# Esquematico_microcotrolador_actuador1.net
KiCad netlist of a schematic drawn in Altium Designer
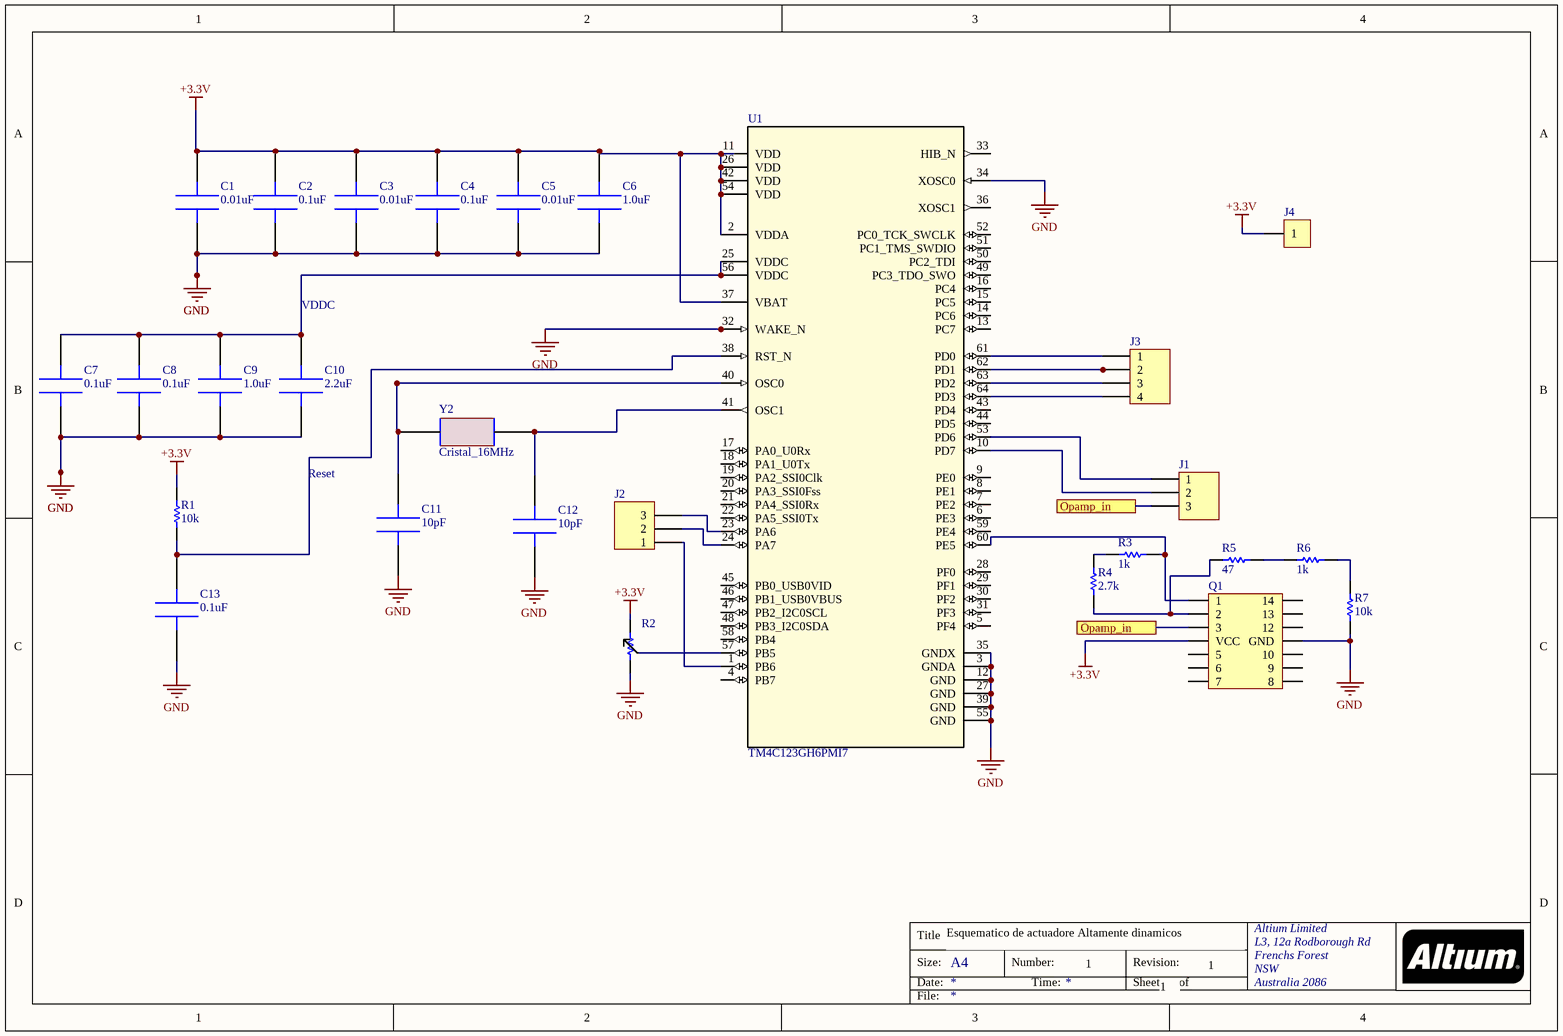
[diagram p0: Esquematico_microcotrolador_actuador1.SchDoc]

(export (version "E")
  (design (tool "Eeschema 10.0.6"))
  (components
    (comp (ref "C1")
      (value "0.01uF")
      (footprint "Capacitor")
      (libsource (lib "esquematicos_librerias") (part "CAP_0.01uF"))
    )
    (comp (ref "C2")
      (value "0.1uF")
      (footprint "Capacitor")
      (libsource (lib "esquematicos_librerias") (part "CAP_0.01uF"))
    )
    (comp (ref "C3")
      (value "0.01uF")
      (footprint "Capacitor")
      (libsource (lib "esquematicos_librerias") (part "CAP_0.01uF"))
    )
    (comp (ref "C4")
      (value "0.1uF")
      (footprint "Capacitor")
      (libsource (lib "esquematicos_librerias") (part "CAP_0.01uF"))
    )
    (comp (ref "C5")
      (value "0.01uF")
      (footprint "Capacitor")
      (libsource (lib "esquematicos_librerias") (part "CAP_0.01uF"))
    )
    (comp (ref "C6")
      (value "1.0uF")
      (footprint "Capacitor")
      (libsource (lib "esquematicos_librerias") (part "CAP_0.01uF"))
    )
    (comp (ref "C7")
      (value "0.1uF")
      (footprint "Capacitor")
      (libsource (lib "esquematicos_librerias") (part "CAP_0.01uF"))
    )
    (comp (ref "C8")
      (value "0.1uF")
      (footprint "Capacitor")
      (libsource (lib "esquematicos_librerias") (part "CAP_0.01uF"))
    )
    (comp (ref "C9")
      (value "1.0uF")
      (footprint "Capacitor")
      (libsource (lib "esquematicos_librerias") (part "CAP_0.01uF"))
    )
    (comp (ref "C10")
      (value "2.2uF")
      (footprint "Capacitor")
      (libsource (lib "esquematicos_librerias") (part "CAP_0.01uF"))
    )
    (comp (ref "C11")
      (value "10pF")
      (footprint "Capacitor")
      (libsource (lib "esquematicos_librerias") (part "CAP_0.01uF"))
    )
    (comp (ref "C12")
      (value "10pF")
      (footprint "Capacitor")
      (libsource (lib "esquematicos_librerias") (part "CAP_0.01uF"))
    )
    (comp (ref "C13")
      (value "0.1uF")
      (footprint "Capacitor")
      (libsource (lib "esquematicos_librerias") (part "CAP_0.01uF"))
    )
    (comp (ref "J1") (value "HEADERS") (footprint "2_PIN_HEADER") (libsource (lib "") (part "HEADERS_1")))
    (comp (ref "J2")
      (value "HEADERS")
      (footprint "2_PIN_HEADER")
      (libsource (lib "esquematicos_librerias") (part "HEADERS"))
    )
    (comp (ref "J3")
      (value "4_HEADERS")
      (footprint "4_HEADERS")
      (libsource (lib "esquematicos_librerias") (part "4_HEADERS"))
    )
    (comp (ref "J4")
      (value "1_HEADER")
      (footprint "1_HEADER")
      (libsource (lib "esquematicos_librerias") (part "1_HEADER"))
    )
    (comp (ref "Q1")
      (value "Op-amp")
      (footprint "Op-amp")
      (libsource (lib "esquematicos_librerias") (part "Op-amp"))
    )
    (comp (ref "R1")
      (value "10k")
      (footprint "resistencia")
      (libsource (lib "esquematicos_librerias") (part "Resisistencia"))
    )
    (comp (ref "R2")
      (value "potenciometro")
      (footprint "Potenciometro")
      (libsource (lib "esquematicos_librerias") (part "potenciometro"))
    )
    (comp (ref "R3")
      (value "1k")
      (footprint "resistencia")
      (libsource (lib "esquematicos_librerias") (part "Resisistencia"))
    )
    (comp (ref "R4")
      (value "2.7k")
      (footprint "resistencia")
      (libsource (lib "esquematicos_librerias") (part "Resisistencia"))
    )
    (comp (ref "R5")
      (value "47")
      (footprint "resistencia")
      (libsource (lib "esquematicos_librerias") (part "Resisistencia"))
    )
    (comp (ref "R6")
      (value "1k")
      (footprint "resistencia")
      (libsource (lib "esquematicos_librerias") (part "Resisistencia"))
    )
    (comp (ref "R7")
      (value "10k")
      (footprint "resistencia")
      (libsource (lib "esquematicos_librerias") (part "Resisistencia"))
    )
    (comp (ref "U1")
      (value "TM4C123GH6PMI7")
      (footprint "PM0064A_N")
      (description "No Description Available")
      (fields
        (field (name "PARTNUMBER") "TM4C123GH6PMTR")
        (field (name "ALTERNATE_PARTNUMBER") "TM4C123GH6PMT")
        (field (name "COPYRIGHT") "Copyright (C) 2021 Ultra Librarian. All rights reserved.")
      )
      (libsource (lib "esquematicos_librerias") (part "TM4C123GH6PMI7"))
    )
    (comp (ref "Y2")
      (value "Cristal_16MHz")
      (footprint "cristal_16MHz")
      (libsource (lib "esquematicos_librerias") (part "Cristal_16MHz"))
    )
  )
  (nets
    (net (code "1") (name "+3.3V") (class "Default")
      (node (ref "C1") (pin "2") (pinfunction "10_2") (pintype "passive"))
      (node (ref "C2") (pin "2") (pinfunction "10_2") (pintype "passive"))
      (node (ref "C3") (pin "2") (pinfunction "10_2") (pintype "passive"))
      (node (ref "C4") (pin "2") (pinfunction "10_2") (pintype "passive"))
      (node (ref "C5") (pin "2") (pinfunction "10_2") (pintype "passive"))
      (node (ref "C6") (pin "2") (pinfunction "10_2") (pintype "passive"))
      (node (ref "J4") (pin "1") (pinfunction "1_1") (pintype "passive"))
      (node (ref "Q1") (pin "4") (pinfunction "VCC_4") (pintype "passive"))
      (node (ref "R1") (pin "2") (pinfunction "2_2") (pintype "passive"))
      (node (ref "R2") (pin "2") (pinfunction "2_2") (pintype "passive"))
      (node (ref "U1") (pin "11") (pinfunction "VDD_11") (pintype "power_in"))
      (node (ref "U1") (pin "2") (pinfunction "VDDA_2") (pintype "power_in"))
      (node (ref "U1") (pin "26") (pinfunction "VDD_26") (pintype "power_in"))
      (node (ref "U1") (pin "37") (pinfunction "VBAT_37") (pintype "power_in"))
      (node (ref "U1") (pin "42") (pinfunction "VDD_42") (pintype "power_in"))
      (node (ref "U1") (pin "54") (pinfunction "VDD_54") (pintype "power_in"))
    )
    (net (code "2") (name "/Opamp_in") (class "Default")
      (node (ref "J1") (pin "3") (pinfunction "3_3") (pintype "passive"))
      (node (ref "Q1") (pin "3") (pinfunction "3_3") (pintype "passive"))
    )
    (net (code "3") (name "GND") (class "Default")
      (node (ref "C1") (pin "1") (pinfunction "9_1") (pintype "passive"))
      (node (ref "C10") (pin "1") (pinfunction "9_1") (pintype "passive"))
      (node (ref "C11") (pin "2") (pinfunction "10_2") (pintype "passive"))
      (node (ref "C12") (pin "2") (pinfunction "10_2") (pintype "passive"))
      (node (ref "C13") (pin "1") (pinfunction "9_1") (pintype "passive"))
      (node (ref "C2") (pin "1") (pinfunction "9_1") (pintype "passive"))
      (node (ref "C3") (pin "1") (pinfunction "9_1") (pintype "passive"))
      (node (ref "C4") (pin "1") (pinfunction "9_1") (pintype "passive"))
      (node (ref "C5") (pin "1") (pinfunction "9_1") (pintype "passive"))
      (node (ref "C6") (pin "1") (pinfunction "9_1") (pintype "passive"))
      (node (ref "C7") (pin "1") (pinfunction "9_1") (pintype "passive"))
      (node (ref "C8") (pin "1") (pinfunction "9_1") (pintype "passive"))
      (node (ref "C9") (pin "1") (pinfunction "9_1") (pintype "passive"))
      (node (ref "Q1") (pin "11") (pinfunction "GND_11") (pintype "passive"))
      (node (ref "R2") (pin "1") (pinfunction "1_1") (pintype "passive"))
      (node (ref "R7") (pin "2") (pinfunction "2_2") (pintype "passive"))
      (node (ref "U1") (pin "12") (pinfunction "GND_12") (pintype "power_in"))
      (node (ref "U1") (pin "27") (pinfunction "GND_27") (pintype "power_in"))
      (node (ref "U1") (pin "3") (pinfunction "GNDA_3") (pintype "power_in"))
      (node (ref "U1") (pin "32") (pinfunction "WAKE_N_32") (pintype "input"))
      (node (ref "U1") (pin "34") (pinfunction "XOSC0_34") (pintype "input"))
      (node (ref "U1") (pin "35") (pinfunction "GNDX_35") (pintype "power_in"))
      (node (ref "U1") (pin "39") (pinfunction "GND_39") (pintype "power_in"))
      (node (ref "U1") (pin "55") (pinfunction "GND_55") (pintype "power_in"))
    )
    (net (code "4") (name "Net-(C10-10)") (class "Default")
      (node (ref "C10") (pin "2") (pinfunction "10_2") (pintype "passive"))
      (node (ref "C7") (pin "2") (pinfunction "10_2") (pintype "passive"))
      (node (ref "C8") (pin "2") (pinfunction "10_2") (pintype "passive"))
      (node (ref "C9") (pin "2") (pinfunction "10_2") (pintype "passive"))
      (node (ref "U1") (pin "25") (pinfunction "VDDC_25") (pintype "power_in"))
      (node (ref "U1") (pin "56") (pinfunction "VDDC_56") (pintype "power_in"))
    )
    (net (code "5") (name "Net-(C11-9)") (class "Default")
      (node (ref "C11") (pin "1") (pinfunction "9_1") (pintype "passive"))
      (node (ref "U1") (pin "40") (pinfunction "OSC0_40") (pintype "input"))
      (node (ref "Y2") (pin "1") (pinfunction "73_1") (pintype "passive"))
    )
    (net (code "6") (name "Net-(C12-9)") (class "Default")
      (node (ref "C12") (pin "1") (pinfunction "9_1") (pintype "passive"))
      (node (ref "U1") (pin "41") (pinfunction "OSC1_41") (pintype "output"))
      (node (ref "Y2") (pin "2") (pinfunction "74_2") (pintype "passive"))
    )
    (net (code "7") (name "Net-(C13-10)") (class "Default")
      (node (ref "C13") (pin "2") (pinfunction "10_2") (pintype "passive"))
      (node (ref "R1") (pin "1") (pinfunction "1_1") (pintype "passive"))
      (node (ref "U1") (pin "38") (pinfunction "RST_N_38") (pintype "input"))
    )
    (net (code "8") (name "Net-(Q1-Pad2)") (class "Default")
      (node (ref "Q1") (pin "2") (pinfunction "2_2") (pintype "passive"))
      (node (ref "R4") (pin "1") (pinfunction "1_1") (pintype "passive"))
      (node (ref "R5") (pin "2") (pinfunction "2_2") (pintype "passive"))
    )
    (net (code "9") (name "Net-(R3-Pad2)") (class "Default")
      (node (ref "R3") (pin "2") (pinfunction "2_2") (pintype "passive"))
      (node (ref "R4") (pin "2") (pinfunction "2_2") (pintype "passive"))
    )
    (net (code "10") (name "Net-(R5-Pad1)") (class "Default")
      (node (ref "R5") (pin "1") (pinfunction "1_1") (pintype "passive"))
      (node (ref "R6") (pin "2") (pinfunction "2_2") (pintype "passive"))
    )
    (net (code "11") (name "Net-(R6-Pad1)") (class "Default")
      (node (ref "R6") (pin "1") (pinfunction "1_1") (pintype "passive"))
      (node (ref "R7") (pin "1") (pinfunction "1_1") (pintype "passive"))
    )
    (net (code "12") (name "Net-(U1-PA6)") (class "Default")
      (node (ref "J2") (pin "3") (pinfunction "3_3") (pintype "passive"))
      (node (ref "U1") (pin "23") (pinfunction "PA6_23") (pintype "bidirectional"))
    )
    (net (code "13") (name "Net-(U1-PA7)") (class "Default")
      (node (ref "J2") (pin "2") (pinfunction "2_2") (pintype "passive"))
      (node (ref "U1") (pin "24") (pinfunction "PA7_24") (pintype "bidirectional"))
    )
    (net (code "14") (name "Net-(U1-PB5)") (class "Default")
      (node (ref "R2") (pin "3") (pinfunction "3_3") (pintype "passive"))
      (node (ref "U1") (pin "57") (pinfunction "PB5_57") (pintype "bidirectional"))
    )
    (net (code "15") (name "Net-(U1-PB6)") (class "Default")
      (node (ref "J2") (pin "1") (pinfunction "1_1") (pintype "passive"))
      (node (ref "U1") (pin "1") (pinfunction "PB6_1") (pintype "bidirectional"))
    )
    (net (code "16") (name "Net-(U1-PD0)") (class "Default")
      (node (ref "J3") (pin "1") (pinfunction "1_1") (pintype "passive"))
      (node (ref "U1") (pin "61") (pinfunction "PD0_61") (pintype "bidirectional"))
    )
    (net (code "17") (name "Net-(U1-PD1)") (class "Default")
      (node (ref "J3") (pin "2") (pinfunction "2_2") (pintype "passive"))
      (node (ref "U1") (pin "62") (pinfunction "PD1_62") (pintype "bidirectional"))
    )
    (net (code "18") (name "Net-(U1-PD2)") (class "Default")
      (node (ref "J3") (pin "3") (pinfunction "3_3") (pintype "passive"))
      (node (ref "U1") (pin "63") (pinfunction "PD2_63") (pintype "bidirectional"))
    )
    (net (code "19") (name "Net-(U1-PD3)") (class "Default")
      (node (ref "J3") (pin "4") (pinfunction "4_4") (pintype "passive"))
      (node (ref "U1") (pin "64") (pinfunction "PD3_64") (pintype "bidirectional"))
    )
    (net (code "20") (name "Net-(U1-PD6)") (class "Default")
      (node (ref "J1") (pin "1") (pinfunction "1_1") (pintype "passive"))
      (node (ref "U1") (pin "53") (pinfunction "PD6_53") (pintype "bidirectional"))
    )
    (net (code "21") (name "Net-(U1-PD7)") (class "Default")
      (node (ref "J1") (pin "2") (pinfunction "2_2") (pintype "passive"))
      (node (ref "U1") (pin "10") (pinfunction "PD7_10") (pintype "bidirectional"))
    )
    (net (code "22") (name "Net-(U1-PE5)") (class "Default")
      (node (ref "Q1") (pin "1") (pinfunction "1_1") (pintype "passive"))
      (node (ref "R3") (pin "1") (pinfunction "1_1") (pintype "passive"))
      (node (ref "U1") (pin "60") (pinfunction "PE5_60") (pintype "bidirectional"))
    )
    (net (code "23") (name "unconnected-(Q1-Pad5)") (class "Default")
      (node (ref "Q1") (pin "5") (pinfunction "5_5") (pintype "passive"))
    )
    (net (code "24") (name "unconnected-(Q1-Pad6)") (class "Default")
      (node (ref "Q1") (pin "6") (pinfunction "6_6") (pintype "passive"))
    )
    (net (code "25") (name "unconnected-(Q1-Pad7)") (class "Default")
      (node (ref "Q1") (pin "7") (pinfunction "7_7") (pintype "passive"))
    )
    (net (code "26") (name "unconnected-(Q1-Pad8)") (class "Default")
      (node (ref "Q1") (pin "8") (pinfunction "8_8") (pintype "passive"))
    )
    (net (code "27") (name "unconnected-(Q1-Pad9)") (class "Default")
      (node (ref "Q1") (pin "9") (pinfunction "9_9") (pintype "passive"))
    )
    (net (code "28") (name "unconnected-(Q1-Pad10)") (class "Default")
      (node (ref "Q1") (pin "10") (pinfunction "10_10") (pintype "passive"))
    )
    (net (code "29") (name "unconnected-(Q1-Pad12)") (class "Default")
      (node (ref "Q1") (pin "12") (pinfunction "12_12") (pintype "passive"))
    )
    (net (code "30") (name "unconnected-(Q1-Pad13)") (class "Default")
      (node (ref "Q1") (pin "13") (pinfunction "13_13") (pintype "passive"))
    )
    (net (code "31") (name "unconnected-(Q1-Pad14)") (class "Default")
      (node (ref "Q1") (pin "14") (pinfunction "14_14") (pintype "passive"))
    )
    (net (code "32") (name "unconnected-(U1-HIB_N-Pad33)") (class "Default")
      (node (ref "U1") (pin "33") (pinfunction "HIB_N_33") (pintype "output"))
    )
    (net (code "33") (name "unconnected-(U1-PA0_U0Rx-Pad17)") (class "Default")
      (node (ref "U1") (pin "17") (pinfunction "PA0_U0Rx_17") (pintype "bidirectional"))
    )
    (net (code "34") (name "unconnected-(U1-PA1_U0Tx-Pad18)") (class "Default")
      (node (ref "U1") (pin "18") (pinfunction "PA1_U0Tx_18") (pintype "bidirectional"))
    )
    (net (code "35") (name "unconnected-(U1-PA2_SSI0Clk-Pad19)") (class "Default")
      (node (ref "U1") (pin "19") (pinfunction "PA2_SSI0Clk_19") (pintype "bidirectional"))
    )
    (net (code "36") (name "unconnected-(U1-PA3_SSI0Fss-Pad20)") (class "Default")
      (node (ref "U1") (pin "20") (pinfunction "PA3_SSI0Fss_20") (pintype "bidirectional"))
    )
    (net (code "37") (name "unconnected-(U1-PA4_SSI0Rx-Pad21)") (class "Default")
      (node (ref "U1") (pin "21") (pinfunction "PA4_SSI0Rx_21") (pintype "bidirectional"))
    )
    (net (code "38") (name "unconnected-(U1-PA5_SSI0Tx-Pad22)") (class "Default")
      (node (ref "U1") (pin "22") (pinfunction "PA5_SSI0Tx_22") (pintype "bidirectional"))
    )
    (net (code "39") (name "unconnected-(U1-PB0_USB0VID-Pad45)") (class "Default")
      (node (ref "U1") (pin "45") (pinfunction "PB0_USB0VID_45") (pintype "bidirectional"))
    )
    (net (code "40") (name "unconnected-(U1-PB1_USB0VBUS-Pad46)") (class "Default")
      (node (ref "U1") (pin "46") (pinfunction "PB1_USB0VBUS_46") (pintype "bidirectional"))
    )
    (net (code "41") (name "unconnected-(U1-PB2_I2C0SCL-Pad47)") (class "Default")
      (node (ref "U1") (pin "47") (pinfunction "PB2_I2C0SCL_47") (pintype "bidirectional"))
    )
    (net (code "42") (name "unconnected-(U1-PB3_I2C0SDA-Pad48)") (class "Default")
      (node (ref "U1") (pin "48") (pinfunction "PB3_I2C0SDA_48") (pintype "bidirectional"))
    )
    (net (code "43") (name "unconnected-(U1-PB4-Pad58)") (class "Default")
      (node (ref "U1") (pin "58") (pinfunction "PB4_58") (pintype "bidirectional"))
    )
    (net (code "44") (name "unconnected-(U1-PB7-Pad4)") (class "Default")
      (node (ref "U1") (pin "4") (pinfunction "PB7_4") (pintype "bidirectional"))
    )
    (net (code "45") (name "unconnected-(U1-PC0_TCK_SWCLK-Pad52)") (class "Default")
      (node (ref "U1") (pin "52") (pinfunction "PC0_TCK_SWCLK_52") (pintype "bidirectional"))
    )
    (net (code "46") (name "unconnected-(U1-PC1_TMS_SWDIO-Pad51)") (class "Default")
      (node (ref "U1") (pin "51") (pinfunction "PC1_TMS_SWDIO_51") (pintype "bidirectional"))
    )
    (net (code "47") (name "unconnected-(U1-PC2_TDI-Pad50)") (class "Default")
      (node (ref "U1") (pin "50") (pinfunction "PC2_TDI_50") (pintype "bidirectional"))
    )
    (net (code "48") (name "unconnected-(U1-PC3_TDO_SWO-Pad49)") (class "Default")
      (node (ref "U1") (pin "49") (pinfunction "PC3_TDO_SWO_49") (pintype "bidirectional"))
    )
    (net (code "49") (name "unconnected-(U1-PC4-Pad16)") (class "Default")
      (node (ref "U1") (pin "16") (pinfunction "PC4_16") (pintype "bidirectional"))
    )
    (net (code "50") (name "unconnected-(U1-PC5-Pad15)") (class "Default")
      (node (ref "U1") (pin "15") (pinfunction "PC5_15") (pintype "bidirectional"))
    )
    (net (code "51") (name "unconnected-(U1-PC6-Pad14)") (class "Default")
      (node (ref "U1") (pin "14") (pinfunction "PC6_14") (pintype "bidirectional"))
    )
    (net (code "52") (name "unconnected-(U1-PC7-Pad13)") (class "Default")
      (node (ref "U1") (pin "13") (pinfunction "PC7_13") (pintype "bidirectional"))
    )
    (net (code "53") (name "unconnected-(U1-PD4-Pad43)") (class "Default")
      (node (ref "U1") (pin "43") (pinfunction "PD4_43") (pintype "bidirectional"))
    )
    (net (code "54") (name "unconnected-(U1-PD5-Pad44)") (class "Default")
      (node (ref "U1") (pin "44") (pinfunction "PD5_44") (pintype "bidirectional"))
    )
    (net (code "55") (name "unconnected-(U1-PE0-Pad9)") (class "Default")
      (node (ref "U1") (pin "9") (pinfunction "PE0_9") (pintype "bidirectional"))
    )
    (net (code "56") (name "unconnected-(U1-PE1-Pad8)") (class "Default")
      (node (ref "U1") (pin "8") (pinfunction "PE1_8") (pintype "bidirectional"))
    )
    (net (code "57") (name "unconnected-(U1-PE2-Pad7)") (class "Default")
      (node (ref "U1") (pin "7") (pinfunction "PE2_7") (pintype "bidirectional"))
    )
    (net (code "58") (name "unconnected-(U1-PE3-Pad6)") (class "Default")
      (node (ref "U1") (pin "6") (pinfunction "PE3_6") (pintype "bidirectional"))
    )
    (net (code "59") (name "unconnected-(U1-PE4-Pad59)") (class "Default")
      (node (ref "U1") (pin "59") (pinfunction "PE4_59") (pintype "bidirectional"))
    )
    (net (code "60") (name "unconnected-(U1-PF0-Pad28)") (class "Default")
      (node (ref "U1") (pin "28") (pinfunction "PF0_28") (pintype "bidirectional"))
    )
    (net (code "61") (name "unconnected-(U1-PF1-Pad29)") (class "Default")
      (node (ref "U1") (pin "29") (pinfunction "PF1_29") (pintype "bidirectional"))
    )
    (net (code "62") (name "unconnected-(U1-PF2-Pad30)") (class "Default")
      (node (ref "U1") (pin "30") (pinfunction "PF2_30") (pintype "bidirectional"))
    )
    (net (code "63") (name "unconnected-(U1-PF3-Pad31)") (class "Default")
      (node (ref "U1") (pin "31") (pinfunction "PF3_31") (pintype "bidirectional"))
    )
    (net (code "64") (name "unconnected-(U1-PF4-Pad5)") (class "Default")
      (node (ref "U1") (pin "5") (pinfunction "PF4_5") (pintype "bidirectional"))
    )
    (net (code "65") (name "unconnected-(U1-XOSC1-Pad36)") (class "Default")
      (node (ref "U1") (pin "36") (pinfunction "XOSC1_36") (pintype "output"))
    )
  )
)
